# Power.net
KiCad netlist of a schematic drawn in Altium Designer
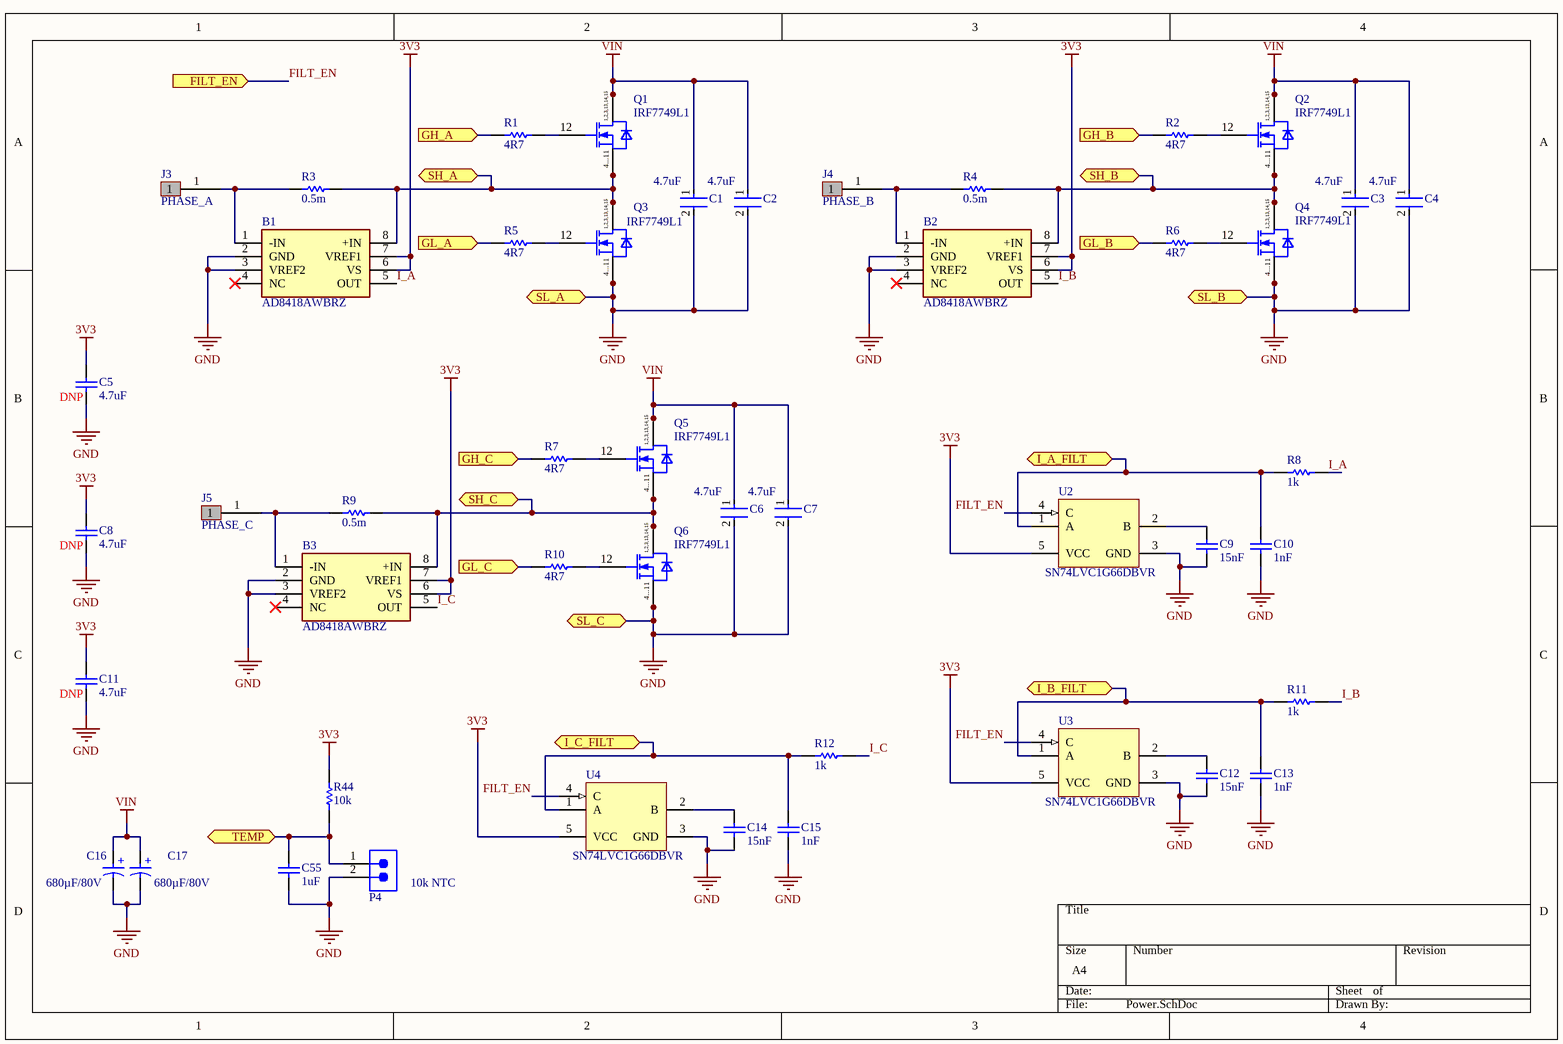
[diagram p0: Power.SchDoc]

(export (version "E")
  (design (tool "Eeschema 10.0.6"))
  (components
    (comp (ref "B1")
      (value "AD8418AWBRZ")
      (footprint "SOP65P490X110-8N")
      (fields (field (name "MOUSER PART NUMBER") "584-AD8418AWBRZ"))
      (libsource (lib "Current_Sense_Amplifiers") (part "AD8418AWBRZ"))
    )
    (comp (ref "B2")
      (value "AD8418AWBRZ")
      (footprint "SOP65P490X110-8N")
      (fields (field (name "MOUSER PART NUMBER") "584-AD8418AWBRZ"))
      (libsource (lib "Current_Sense_Amplifiers") (part "AD8418AWBRZ"))
    )
    (comp (ref "B3")
      (value "AD8418AWBRZ")
      (footprint "SOP65P490X110-8N")
      (fields (field (name "MOUSER PART NUMBER") "584-AD8418AWBRZ"))
      (libsource (lib "Current_Sense_Amplifiers") (part "AD8418AWBRZ"))
    )
    (comp (ref "C1")
      (value "HMK325C7475KN-TE")
      (footprint "FP-1210-L_3_2_0_3-W_2_5_0-IPC_A")
      (description "None")
      (fields (field (name "CAPACITANCE") "4.7uF") (field (name "TOLERANCE") "10%"))
      (libsource (lib "Altium Content Vault") (part "02cd4be3c70576c341d710602a673aa"))
    )
    (comp (ref "C2")
      (value "HMK325C7475KN-TE")
      (footprint "FP-1210-L_3_2_0_3-W_2_5_0-IPC_A")
      (description "None")
      (fields (field (name "CAPACITANCE") "4.7uF") (field (name "TOLERANCE") "10%"))
      (libsource (lib "Altium Content Vault") (part "02cd4be3c70576c341d710602a673aa"))
    )
    (comp (ref "C3")
      (value "HMK325C7475KN-TE")
      (footprint "FP-1210-L_3_2_0_3-W_2_5_0-IPC_A")
      (description "None")
      (fields (field (name "CAPACITANCE") "4.7uF") (field (name "TOLERANCE") "10%"))
      (libsource (lib "Altium Content Vault") (part "02cd4be3c70576c341d710602a673aa"))
    )
    (comp (ref "C4")
      (value "HMK325C7475KN-TE")
      (footprint "FP-1210-L_3_2_0_3-W_2_5_0-IPC_A")
      (description "None")
      (fields (field (name "CAPACITANCE") "4.7uF") (field (name "TOLERANCE") "10%"))
      (libsource (lib "Altium Content Vault") (part "02cd4be3c70576c341d710602a673aa"))
    )
    (comp (ref "C5")
      (value "4.7uF")
      (footprint "Wurth 0603 capacitor")
      (fields (field (name "Comment") "Generic Capacitor 4.7uF 0603"))
      (libsource (lib "Passives") (part "Generic Capacitor 4.7uF 0603"))
    )
    (comp (ref "C6")
      (value "HMK325C7475KN-TE")
      (footprint "FP-1210-L_3_2_0_3-W_2_5_0-IPC_A")
      (description "None")
      (fields (field (name "CAPACITANCE") "4.7uF") (field (name "TOLERANCE") "10%"))
      (libsource (lib "Altium Content Vault") (part "02cd4be3c70576c341d710602a673aa"))
    )
    (comp (ref "C7")
      (value "HMK325C7475KN-TE")
      (footprint "FP-1210-L_3_2_0_3-W_2_5_0-IPC_A")
      (description "None")
      (fields (field (name "CAPACITANCE") "4.7uF") (field (name "TOLERANCE") "10%"))
      (libsource (lib "Altium Content Vault") (part "02cd4be3c70576c341d710602a673aa"))
    )
    (comp (ref "C8")
      (value "4.7uF")
      (footprint "Wurth 0603 capacitor")
      (fields (field (name "Comment") "Generic Capacitor 4.7uF 0603"))
      (libsource (lib "Passives") (part "Generic Capacitor 4.7uF 0603"))
    )
    (comp (ref "C9")
      (value "15nF")
      (footprint "Wurth 0603 capacitor")
      (fields (field (name "Comment") "Generic Capacitor 15nF 0603"))
      (libsource (lib "Passives") (part "Generic Capacitor 15nF 0603"))
    )
    (comp (ref "C10")
      (value "1nF")
      (footprint "Wurth 0603 capacitor")
      (fields (field (name "Comment") "Generic Capacitor 1nF 0603"))
      (libsource (lib "Passives") (part "Generic Capacitor 1nF 0603"))
    )
    (comp (ref "C11")
      (value "4.7uF")
      (footprint "Wurth 0603 capacitor")
      (fields (field (name "Comment") "Generic Capacitor 4.7uF 0603"))
      (libsource (lib "Passives") (part "Generic Capacitor 4.7uF 0603"))
    )
    (comp (ref "C12")
      (value "15nF")
      (footprint "Wurth 0603 capacitor")
      (fields (field (name "Comment") "Generic Capacitor 15nF 0603"))
      (libsource (lib "Passives") (part "Generic Capacitor 15nF 0603"))
    )
    (comp (ref "C13")
      (value "1nF")
      (footprint "Wurth 0603 capacitor")
      (fields (field (name "Comment") "Generic Capacitor 1nF 0603"))
      (libsource (lib "Passives") (part "Generic Capacitor 1nF 0603"))
    )
    (comp (ref "C14")
      (value "15nF")
      (footprint "Wurth 0603 capacitor")
      (fields (field (name "Comment") "Generic Capacitor 15nF 0603"))
      (libsource (lib "Passives") (part "Generic Capacitor 15nF 0603"))
    )
    (comp (ref "C15")
      (value "1nF")
      (footprint "Wurth 0603 capacitor")
      (fields (field (name "Comment") "Generic Capacitor 1nF 0603"))
      (libsource (lib "Passives") (part "Generic Capacitor 1nF 0603"))
    )
    (comp (ref "C16")
      (value "680µF/80V")
      (footprint "WURTH THT CAP D18H25 - sideways")
      (description "Bulk/Capacitor, Aluminum, 80 V, Cap.680 , Dia.18 , Leng.25 ¦Chemi-Con EKY-800ELL681MM25S")
      (fields
        (field (name "MANUFACTURER") "United Chemi-Con")
        (field (name "MANUFACTURER PART NUMBER") "EKY-800ELL681MM25S")
      )
      (libsource (lib "Passives") (part "NCC 680uF/80V TH"))
    )
    (comp (ref "C17")
      (value "680µF/80V")
      (footprint "WURTH THT CAP D18H25 - sideways")
      (description "Bulk/Capacitor, Aluminum, 80 V, Cap.680 , Dia.18 , Leng.25 ¦Chemi-Con EKY-800ELL681MM25S")
      (fields
        (field (name "MANUFACTURER") "United Chemi-Con")
        (field (name "MANUFACTURER PART NUMBER") "EKY-800ELL681MM25S")
      )
      (libsource (lib "Passives") (part "NCC 680uF/80V TH"))
    )
    (comp (ref "C55")
      (value "1uF")
      (footprint "Wurth 0603 capacitor")
      (fields (field (name "Comment") "Generic Capacitor 1uF 0603"))
      (libsource (lib "Passives") (part "Generic Capacitor 1uF 0603"))
    )
    (comp (ref "J3")
      (value "PHASE_A")
      (footprint "Solder Pad 3X4MM")
      (libsource (lib "Connectors") (part "Solder pad"))
    )
    (comp (ref "J4")
      (value "PHASE_B")
      (footprint "Solder Pad 3X4MM")
      (libsource (lib "Connectors") (part "Solder pad"))
    )
    (comp (ref "J5")
      (value "PHASE_C")
      (footprint "Solder Pad 3X4MM")
      (libsource (lib "Connectors") (part "Solder pad"))
    )
    (comp (ref "P4")
      (value "61300211121")
      (footprint "2x1 2.54mm F")
      (description "WR-PHD Pin Header, THT, Vertical, pitch 2.54mm, 1 Row, 2P")
      (fields (field (name "MANUFACTURER") "Wurth Elektronik"))
      (libsource (lib "2.54mm_pin_headers") (part "2P"))
    )
    (comp (ref "Q1")
      (value "IRF7749L1")
      (footprint "INFINEON DIRECTFET-L8-V")
      (fields (field (name "MANUFACTURER") "Infineon Technologies"))
      (libsource (lib "N_CHN_FET") (part "IRF7749L1"))
    )
    (comp (ref "Q2")
      (value "IRF7749L1")
      (footprint "INFINEON DIRECTFET-L8-V")
      (fields (field (name "MANUFACTURER") "Infineon Technologies"))
      (libsource (lib "N_CHN_FET") (part "IRF7749L1"))
    )
    (comp (ref "Q3")
      (value "IRF7749L1")
      (footprint "INFINEON DIRECTFET-L8-V")
      (fields (field (name "MANUFACTURER") "Infineon Technologies"))
      (libsource (lib "N_CHN_FET") (part "IRF7749L1"))
    )
    (comp (ref "Q4")
      (value "IRF7749L1")
      (footprint "INFINEON DIRECTFET-L8-V")
      (fields (field (name "MANUFACTURER") "Infineon Technologies"))
      (libsource (lib "N_CHN_FET") (part "IRF7749L1"))
    )
    (comp (ref "Q5")
      (value "IRF7749L1")
      (footprint "INFINEON DIRECTFET-L8-V")
      (fields (field (name "MANUFACTURER") "Infineon Technologies"))
      (libsource (lib "N_CHN_FET") (part "IRF7749L1"))
    )
    (comp (ref "Q6")
      (value "IRF7749L1")
      (footprint "INFINEON DIRECTFET-L8-V")
      (fields (field (name "MANUFACTURER") "Infineon Technologies"))
      (libsource (lib "N_CHN_FET") (part "IRF7749L1"))
    )
    (comp (ref "R1")
      (value "4R7")
      (footprint "Wurth 0603 Resistor")
      (fields (field (name "Comment") "Generic Resistor 4k7 0603"))
      (libsource (lib "Passives") (part "Generic Resistor 4R7 0603"))
    )
    (comp (ref "R2")
      (value "4R7")
      (footprint "Wurth 0603 Resistor")
      (fields (field (name "Comment") "Generic Resistor 4k7 0603"))
      (libsource (lib "Passives") (part "Generic Resistor 4R7 0603"))
    )
    (comp (ref "R3")
      (value "0.5m")
      (footprint "WURTH 2512 RESISTOR")
      (description "6W 0.5mΩ Patch Splitter ±115ppm/℃ ±1% 2512 Current Sense Resistors / Shunt Resistors ROHS")
      (fields (field (name "Comment") "Yezhan ASR-M-3-0.5F"))
      (libsource (lib "Shunt_Resistors") (part "Yezhan ASR-M-3-0.5F"))
    )
    (comp (ref "R4")
      (value "0.5m")
      (footprint "WURTH 2512 RESISTOR")
      (description "6W 0.5mΩ Patch Splitter ±115ppm/℃ ±1% 2512 Current Sense Resistors / Shunt Resistors ROHS")
      (fields (field (name "Comment") "Yezhan ASR-M-3-0.5F"))
      (libsource (lib "Shunt_Resistors") (part "Yezhan ASR-M-3-0.5F"))
    )
    (comp (ref "R5")
      (value "4R7")
      (footprint "Wurth 0603 Resistor")
      (fields (field (name "Comment") "Generic Resistor 4k7 0603"))
      (libsource (lib "Passives") (part "Generic Resistor 4R7 0603"))
    )
    (comp (ref "R6")
      (value "4R7")
      (footprint "Wurth 0603 Resistor")
      (fields (field (name "Comment") "Generic Resistor 4k7 0603"))
      (libsource (lib "Passives") (part "Generic Resistor 4R7 0603"))
    )
    (comp (ref "R7")
      (value "4R7")
      (footprint "Wurth 0603 Resistor")
      (fields (field (name "Comment") "Generic Resistor 4k7 0603"))
      (libsource (lib "Passives") (part "Generic Resistor 4R7 0603"))
    )
    (comp (ref "R8")
      (value "1k")
      (footprint "Wurth 0603 Resistor")
      (fields (field (name "Comment") "Generic Resistor 1k 0603"))
      (libsource (lib "Passives") (part "Generic Resistor 1k 0603"))
    )
    (comp (ref "R9")
      (value "0.5m")
      (footprint "WURTH 2512 RESISTOR")
      (description "6W 0.5mΩ Patch Splitter ±115ppm/℃ ±1% 2512 Current Sense Resistors / Shunt Resistors ROHS")
      (fields (field (name "Comment") "Yezhan ASR-M-3-0.5F"))
      (libsource (lib "Shunt_Resistors") (part "Yezhan ASR-M-3-0.5F"))
    )
    (comp (ref "R10")
      (value "4R7")
      (footprint "Wurth 0603 Resistor")
      (fields (field (name "Comment") "Generic Resistor 4k7 0603"))
      (libsource (lib "Passives") (part "Generic Resistor 4R7 0603"))
    )
    (comp (ref "R11")
      (value "1k")
      (footprint "Wurth 0603 Resistor")
      (fields (field (name "Comment") "Generic Resistor 1k 0603"))
      (libsource (lib "Passives") (part "Generic Resistor 1k 0603"))
    )
    (comp (ref "R12")
      (value "1k")
      (footprint "Wurth 0603 Resistor")
      (fields (field (name "Comment") "Generic Resistor 1k 0603"))
      (libsource (lib "Passives") (part "Generic Resistor 1k 0603"))
    )
    (comp (ref "R44")
      (value "10k")
      (footprint "Wurth 0603 Resistor")
      (fields (field (name "Comment") "Generic Resistor 10k 0603"))
      (libsource (lib "Passives") (part "Generic Resistor 10k 0603"))
    )
    (comp (ref "U2")
      (value "SN74LVC1G66DBVR")
      (footprint "DBV0005A_L")
      (description "Single Analog Switch, DBV0005A, LARGE T&R")
      (fields
        (field (name "GENERIC PART NUMBER") "SN74LVC1G66")
        (field (name "MANUFACTURER") "Texas Instruments")
      )
      (libsource (lib "Altium Content Vault") (part "TI-SN74XXC1G66-5"))
    )
    (comp (ref "U3")
      (value "SN74LVC1G66DBVR")
      (footprint "DBV0005A_L")
      (description "Single Analog Switch, DBV0005A, LARGE T&R")
      (fields
        (field (name "GENERIC PART NUMBER") "SN74LVC1G66")
        (field (name "MANUFACTURER") "Texas Instruments")
      )
      (libsource (lib "Altium Content Vault") (part "TI-SN74XXC1G66-5"))
    )
    (comp (ref "U4")
      (value "SN74LVC1G66DBVR")
      (footprint "DBV0005A_L")
      (description "Single Analog Switch, DBV0005A, LARGE T&R")
      (fields
        (field (name "GENERIC PART NUMBER") "SN74LVC1G66")
        (field (name "MANUFACTURER") "Texas Instruments")
      )
      (libsource (lib "Altium Content Vault") (part "TI-SN74XXC1G66-5"))
    )
  )
  (nets
    (net (code "1") (name "/FILT_EN") (class "Default")
      (node (ref "U2") (pin "4") (pinfunction "C_4") (pintype "input"))
      (node (ref "U3") (pin "4") (pinfunction "C_4") (pintype "input"))
      (node (ref "U4") (pin "4") (pinfunction "C_4") (pintype "input"))
    )
    (net (code "2") (name "/GH_A") (class "Default")
      (node (ref "R1") (pin "1") (pinfunction "1_1") (pintype "passive"))
    )
    (net (code "3") (name "/GH_B") (class "Default")
      (node (ref "R2") (pin "1") (pinfunction "1_1") (pintype "passive"))
    )
    (net (code "4") (name "/GH_C") (class "Default")
      (node (ref "R7") (pin "1") (pinfunction "1_1") (pintype "passive"))
    )
    (net (code "5") (name "/GL_A") (class "Default")
      (node (ref "R5") (pin "1") (pinfunction "1_1") (pintype "passive"))
    )
    (net (code "6") (name "/GL_B") (class "Default")
      (node (ref "R6") (pin "1") (pinfunction "1_1") (pintype "passive"))
    )
    (net (code "7") (name "/GL_C") (class "Default")
      (node (ref "R10") (pin "1") (pinfunction "1_1") (pintype "passive"))
    )
    (net (code "8") (name "/I_A") (class "Default")
      (node (ref "B1") (pin "5") (pinfunction "OUT_5") (pintype "passive"))
      (node (ref "R8") (pin "2") (pinfunction "2_2") (pintype "passive"))
    )
    (net (code "9") (name "/I_A_FILT") (class "Default")
      (node (ref "C10") (pin "2") (pinfunction "2_2") (pintype "passive"))
      (node (ref "R8") (pin "1") (pinfunction "1_1") (pintype "passive"))
      (node (ref "U2") (pin "1") (pinfunction "A_1") (pintype "passive"))
    )
    (net (code "10") (name "/I_B") (class "Default")
      (node (ref "B2") (pin "5") (pinfunction "OUT_5") (pintype "passive"))
      (node (ref "R11") (pin "2") (pinfunction "2_2") (pintype "passive"))
    )
    (net (code "11") (name "/I_B_FILT") (class "Default")
      (node (ref "C13") (pin "2") (pinfunction "2_2") (pintype "passive"))
      (node (ref "R11") (pin "1") (pinfunction "1_1") (pintype "passive"))
      (node (ref "U3") (pin "1") (pinfunction "A_1") (pintype "passive"))
    )
    (net (code "12") (name "/I_C") (class "Default")
      (node (ref "B3") (pin "5") (pinfunction "OUT_5") (pintype "passive"))
      (node (ref "R12") (pin "2") (pinfunction "2_2") (pintype "passive"))
    )
    (net (code "13") (name "/I_C_FILT") (class "Default")
      (node (ref "C15") (pin "2") (pinfunction "2_2") (pintype "passive"))
      (node (ref "R12") (pin "1") (pinfunction "1_1") (pintype "passive"))
      (node (ref "U4") (pin "1") (pinfunction "A_1") (pintype "passive"))
    )
    (net (code "14") (name "/SH_A") (class "Default")
      (node (ref "B1") (pin "8") (pinfunction "+IN_8") (pintype "passive"))
      (node (ref "Q1") (pin "10") (pinfunction "SOURCE7_10") (pintype "passive"))
      (node (ref "Q1") (pin "11") (pinfunction "SOURCE8_11") (pintype "passive"))
      (node (ref "Q1") (pin "4") (pinfunction "SOURCE1_4") (pintype "passive"))
      (node (ref "Q1") (pin "5") (pinfunction "SOURCE2_5") (pintype "passive"))
      (node (ref "Q1") (pin "6") (pinfunction "SOURCE3_6") (pintype "passive"))
      (node (ref "Q1") (pin "7") (pinfunction "SOURCE4_7") (pintype "passive"))
      (node (ref "Q1") (pin "8") (pinfunction "SOURCE5_8") (pintype "passive"))
      (node (ref "Q1") (pin "9") (pinfunction "SOURCE6_9") (pintype "passive"))
      (node (ref "Q3") (pin "1") (pinfunction "DRAIN1_1") (pintype "passive"))
      (node (ref "Q3") (pin "13") (pinfunction "DRAIN4_13") (pintype "passive"))
      (node (ref "Q3") (pin "14") (pinfunction "DRAIN5_14") (pintype "passive"))
      (node (ref "Q3") (pin "15") (pinfunction "DRAIN6_15") (pintype "passive"))
      (node (ref "Q3") (pin "2") (pinfunction "DRAIN2_2") (pintype "passive"))
      (node (ref "Q3") (pin "3") (pinfunction "DRAIN3_3") (pintype "passive"))
      (node (ref "R3") (pin "2") (pinfunction "2_2") (pintype "passive"))
    )
    (net (code "15") (name "/SH_B") (class "Default")
      (node (ref "B2") (pin "8") (pinfunction "+IN_8") (pintype "passive"))
      (node (ref "Q2") (pin "10") (pinfunction "SOURCE7_10") (pintype "passive"))
      (node (ref "Q2") (pin "11") (pinfunction "SOURCE8_11") (pintype "passive"))
      (node (ref "Q2") (pin "4") (pinfunction "SOURCE1_4") (pintype "passive"))
      (node (ref "Q2") (pin "5") (pinfunction "SOURCE2_5") (pintype "passive"))
      (node (ref "Q2") (pin "6") (pinfunction "SOURCE3_6") (pintype "passive"))
      (node (ref "Q2") (pin "7") (pinfunction "SOURCE4_7") (pintype "passive"))
      (node (ref "Q2") (pin "8") (pinfunction "SOURCE5_8") (pintype "passive"))
      (node (ref "Q2") (pin "9") (pinfunction "SOURCE6_9") (pintype "passive"))
      (node (ref "Q4") (pin "1") (pinfunction "DRAIN1_1") (pintype "passive"))
      (node (ref "Q4") (pin "13") (pinfunction "DRAIN4_13") (pintype "passive"))
      (node (ref "Q4") (pin "14") (pinfunction "DRAIN5_14") (pintype "passive"))
      (node (ref "Q4") (pin "15") (pinfunction "DRAIN6_15") (pintype "passive"))
      (node (ref "Q4") (pin "2") (pinfunction "DRAIN2_2") (pintype "passive"))
      (node (ref "Q4") (pin "3") (pinfunction "DRAIN3_3") (pintype "passive"))
      (node (ref "R4") (pin "2") (pinfunction "2_2") (pintype "passive"))
    )
    (net (code "16") (name "/SH_C") (class "Default")
      (node (ref "B3") (pin "8") (pinfunction "+IN_8") (pintype "passive"))
      (node (ref "Q5") (pin "10") (pinfunction "SOURCE7_10") (pintype "passive"))
      (node (ref "Q5") (pin "11") (pinfunction "SOURCE8_11") (pintype "passive"))
      (node (ref "Q5") (pin "4") (pinfunction "SOURCE1_4") (pintype "passive"))
      (node (ref "Q5") (pin "5") (pinfunction "SOURCE2_5") (pintype "passive"))
      (node (ref "Q5") (pin "6") (pinfunction "SOURCE3_6") (pintype "passive"))
      (node (ref "Q5") (pin "7") (pinfunction "SOURCE4_7") (pintype "passive"))
      (node (ref "Q5") (pin "8") (pinfunction "SOURCE5_8") (pintype "passive"))
      (node (ref "Q5") (pin "9") (pinfunction "SOURCE6_9") (pintype "passive"))
      (node (ref "Q6") (pin "1") (pinfunction "DRAIN1_1") (pintype "passive"))
      (node (ref "Q6") (pin "13") (pinfunction "DRAIN4_13") (pintype "passive"))
      (node (ref "Q6") (pin "14") (pinfunction "DRAIN5_14") (pintype "passive"))
      (node (ref "Q6") (pin "15") (pinfunction "DRAIN6_15") (pintype "passive"))
      (node (ref "Q6") (pin "2") (pinfunction "DRAIN2_2") (pintype "passive"))
      (node (ref "Q6") (pin "3") (pinfunction "DRAIN3_3") (pintype "passive"))
      (node (ref "R9") (pin "2") (pinfunction "2_2") (pintype "passive"))
    )
    (net (code "17") (name "/TEMP") (class "Default")
      (node (ref "C55") (pin "2") (pinfunction "2_2") (pintype "passive"))
      (node (ref "P4") (pin "1") (pinfunction "1_1") (pintype "passive"))
      (node (ref "R44") (pin "1") (pinfunction "1_1") (pintype "passive"))
    )
    (net (code "18") (name "3V3") (class "Default")
      (node (ref "B1") (pin "6") (pinfunction "VS_6") (pintype "passive"))
      (node (ref "B1") (pin "7") (pinfunction "VREF1_7") (pintype "passive"))
      (node (ref "B2") (pin "6") (pinfunction "VS_6") (pintype "passive"))
      (node (ref "B2") (pin "7") (pinfunction "VREF1_7") (pintype "passive"))
      (node (ref "B3") (pin "6") (pinfunction "VS_6") (pintype "passive"))
      (node (ref "B3") (pin "7") (pinfunction "VREF1_7") (pintype "passive"))
      (node (ref "C11") (pin "2") (pinfunction "2_2") (pintype "passive"))
      (node (ref "C5") (pin "2") (pinfunction "2_2") (pintype "passive"))
      (node (ref "C8") (pin "2") (pinfunction "2_2") (pintype "passive"))
      (node (ref "R44") (pin "2") (pinfunction "2_2") (pintype "passive"))
      (node (ref "U2") (pin "5") (pinfunction "VCC_5") (pintype "power_in"))
      (node (ref "U3") (pin "5") (pinfunction "VCC_5") (pintype "power_in"))
      (node (ref "U4") (pin "5") (pinfunction "VCC_5") (pintype "power_in"))
    )
    (net (code "19") (name "GND") (class "Default")
      (node (ref "B1") (pin "2") (pinfunction "GND_2") (pintype "passive"))
      (node (ref "B1") (pin "3") (pinfunction "VREF2_3") (pintype "passive"))
      (node (ref "B2") (pin "2") (pinfunction "GND_2") (pintype "passive"))
      (node (ref "B2") (pin "3") (pinfunction "VREF2_3") (pintype "passive"))
      (node (ref "B3") (pin "2") (pinfunction "GND_2") (pintype "passive"))
      (node (ref "B3") (pin "3") (pinfunction "VREF2_3") (pintype "passive"))
      (node (ref "C1") (pin "2") (pinfunction "2_2") (pintype "passive"))
      (node (ref "C10") (pin "1") (pinfunction "1_1") (pintype "passive"))
      (node (ref "C11") (pin "1") (pinfunction "1_1") (pintype "passive"))
      (node (ref "C12") (pin "1") (pinfunction "1_1") (pintype "passive"))
      (node (ref "C13") (pin "1") (pinfunction "1_1") (pintype "passive"))
      (node (ref "C14") (pin "1") (pinfunction "1_1") (pintype "passive"))
      (node (ref "C15") (pin "1") (pinfunction "1_1") (pintype "passive"))
      (node (ref "C16") (pin "2") (pinfunction "N_2") (pintype "passive"))
      (node (ref "C17") (pin "2") (pinfunction "N_2") (pintype "passive"))
      (node (ref "C2") (pin "2") (pinfunction "2_2") (pintype "passive"))
      (node (ref "C3") (pin "2") (pinfunction "2_2") (pintype "passive"))
      (node (ref "C4") (pin "2") (pinfunction "2_2") (pintype "passive"))
      (node (ref "C5") (pin "1") (pinfunction "1_1") (pintype "passive"))
      (node (ref "C55") (pin "1") (pinfunction "1_1") (pintype "passive"))
      (node (ref "C6") (pin "2") (pinfunction "2_2") (pintype "passive"))
      (node (ref "C7") (pin "2") (pinfunction "2_2") (pintype "passive"))
      (node (ref "C8") (pin "1") (pinfunction "1_1") (pintype "passive"))
      (node (ref "C9") (pin "1") (pinfunction "1_1") (pintype "passive"))
      (node (ref "P4") (pin "2") (pinfunction "2_2") (pintype "passive"))
      (node (ref "Q3") (pin "10") (pinfunction "SOURCE7_10") (pintype "passive"))
      (node (ref "Q3") (pin "11") (pinfunction "SOURCE8_11") (pintype "passive"))
      (node (ref "Q3") (pin "4") (pinfunction "SOURCE1_4") (pintype "passive"))
      (node (ref "Q3") (pin "5") (pinfunction "SOURCE2_5") (pintype "passive"))
      (node (ref "Q3") (pin "6") (pinfunction "SOURCE3_6") (pintype "passive"))
      (node (ref "Q3") (pin "7") (pinfunction "SOURCE4_7") (pintype "passive"))
      (node (ref "Q3") (pin "8") (pinfunction "SOURCE5_8") (pintype "passive"))
      (node (ref "Q3") (pin "9") (pinfunction "SOURCE6_9") (pintype "passive"))
      (node (ref "Q4") (pin "10") (pinfunction "SOURCE7_10") (pintype "passive"))
      (node (ref "Q4") (pin "11") (pinfunction "SOURCE8_11") (pintype "passive"))
      (node (ref "Q4") (pin "4") (pinfunction "SOURCE1_4") (pintype "passive"))
      (node (ref "Q4") (pin "5") (pinfunction "SOURCE2_5") (pintype "passive"))
      (node (ref "Q4") (pin "6") (pinfunction "SOURCE3_6") (pintype "passive"))
      (node (ref "Q4") (pin "7") (pinfunction "SOURCE4_7") (pintype "passive"))
      (node (ref "Q4") (pin "8") (pinfunction "SOURCE5_8") (pintype "passive"))
      (node (ref "Q4") (pin "9") (pinfunction "SOURCE6_9") (pintype "passive"))
      (node (ref "Q6") (pin "10") (pinfunction "SOURCE7_10") (pintype "passive"))
      (node (ref "Q6") (pin "11") (pinfunction "SOURCE8_11") (pintype "passive"))
      (node (ref "Q6") (pin "4") (pinfunction "SOURCE1_4") (pintype "passive"))
      (node (ref "Q6") (pin "5") (pinfunction "SOURCE2_5") (pintype "passive"))
      (node (ref "Q6") (pin "6") (pinfunction "SOURCE3_6") (pintype "passive"))
      (node (ref "Q6") (pin "7") (pinfunction "SOURCE4_7") (pintype "passive"))
      (node (ref "Q6") (pin "8") (pinfunction "SOURCE5_8") (pintype "passive"))
      (node (ref "Q6") (pin "9") (pinfunction "SOURCE6_9") (pintype "passive"))
      (node (ref "U2") (pin "3") (pinfunction "GND_3") (pintype "power_in"))
      (node (ref "U3") (pin "3") (pinfunction "GND_3") (pintype "power_in"))
      (node (ref "U4") (pin "3") (pinfunction "GND_3") (pintype "power_in"))
    )
    (net (code "20") (name "Net-(B1--IN)") (class "Default")
      (node (ref "B1") (pin "1") (pinfunction "-IN_1") (pintype "passive"))
      (node (ref "J3") (pin "1") (pinfunction "1_1") (pintype "passive"))
      (node (ref "R3") (pin "1") (pinfunction "1_1") (pintype "passive"))
    )
    (net (code "21") (name "Net-(B2--IN)") (class "Default")
      (node (ref "B2") (pin "1") (pinfunction "-IN_1") (pintype "passive"))
      (node (ref "J4") (pin "1") (pinfunction "1_1") (pintype "passive"))
      (node (ref "R4") (pin "1") (pinfunction "1_1") (pintype "passive"))
    )
    (net (code "22") (name "Net-(B3--IN)") (class "Default")
      (node (ref "B3") (pin "1") (pinfunction "-IN_1") (pintype "passive"))
      (node (ref "J5") (pin "1") (pinfunction "1_1") (pintype "passive"))
      (node (ref "R9") (pin "1") (pinfunction "1_1") (pintype "passive"))
    )
    (net (code "23") (name "Net-(Q1-GATE)") (class "Default")
      (node (ref "Q1") (pin "12") (pinfunction "GATE_12") (pintype "passive"))
      (node (ref "R1") (pin "2") (pinfunction "2_2") (pintype "passive"))
    )
    (net (code "24") (name "Net-(Q2-GATE)") (class "Default")
      (node (ref "Q2") (pin "12") (pinfunction "GATE_12") (pintype "passive"))
      (node (ref "R2") (pin "2") (pinfunction "2_2") (pintype "passive"))
    )
    (net (code "25") (name "Net-(Q3-GATE)") (class "Default")
      (node (ref "Q3") (pin "12") (pinfunction "GATE_12") (pintype "passive"))
      (node (ref "R5") (pin "2") (pinfunction "2_2") (pintype "passive"))
    )
    (net (code "26") (name "Net-(Q4-GATE)") (class "Default")
      (node (ref "Q4") (pin "12") (pinfunction "GATE_12") (pintype "passive"))
      (node (ref "R6") (pin "2") (pinfunction "2_2") (pintype "passive"))
    )
    (net (code "27") (name "Net-(Q5-GATE)") (class "Default")
      (node (ref "Q5") (pin "12") (pinfunction "GATE_12") (pintype "passive"))
      (node (ref "R7") (pin "2") (pinfunction "2_2") (pintype "passive"))
    )
    (net (code "28") (name "Net-(Q6-GATE)") (class "Default")
      (node (ref "Q6") (pin "12") (pinfunction "GATE_12") (pintype "passive"))
      (node (ref "R10") (pin "2") (pinfunction "2_2") (pintype "passive"))
    )
    (net (code "29") (name "Net-(U2-B)") (class "Default")
      (node (ref "C9") (pin "2") (pinfunction "2_2") (pintype "passive"))
      (node (ref "U2") (pin "2") (pinfunction "B_2") (pintype "passive"))
    )
    (net (code "30") (name "Net-(U3-B)") (class "Default")
      (node (ref "C12") (pin "2") (pinfunction "2_2") (pintype "passive"))
      (node (ref "U3") (pin "2") (pinfunction "B_2") (pintype "passive"))
    )
    (net (code "31") (name "Net-(U4-B)") (class "Default")
      (node (ref "C14") (pin "2") (pinfunction "2_2") (pintype "passive"))
      (node (ref "U4") (pin "2") (pinfunction "B_2") (pintype "passive"))
    )
    (net (code "32") (name "VIN") (class "Default")
      (node (ref "C1") (pin "1") (pinfunction "1_1") (pintype "passive"))
      (node (ref "C16") (pin "1") (pinfunction "P_1") (pintype "passive"))
      (node (ref "C17") (pin "1") (pinfunction "P_1") (pintype "passive"))
      (node (ref "C2") (pin "1") (pinfunction "1_1") (pintype "passive"))
      (node (ref "C3") (pin "1") (pinfunction "1_1") (pintype "passive"))
      (node (ref "C4") (pin "1") (pinfunction "1_1") (pintype "passive"))
      (node (ref "C6") (pin "1") (pinfunction "1_1") (pintype "passive"))
      (node (ref "C7") (pin "1") (pinfunction "1_1") (pintype "passive"))
      (node (ref "Q1") (pin "1") (pinfunction "DRAIN1_1") (pintype "passive"))
      (node (ref "Q1") (pin "13") (pinfunction "DRAIN4_13") (pintype "passive"))
      (node (ref "Q1") (pin "14") (pinfunction "DRAIN5_14") (pintype "passive"))
      (node (ref "Q1") (pin "15") (pinfunction "DRAIN6_15") (pintype "passive"))
      (node (ref "Q1") (pin "2") (pinfunction "DRAIN2_2") (pintype "passive"))
      (node (ref "Q1") (pin "3") (pinfunction "DRAIN3_3") (pintype "passive"))
      (node (ref "Q2") (pin "1") (pinfunction "DRAIN1_1") (pintype "passive"))
      (node (ref "Q2") (pin "13") (pinfunction "DRAIN4_13") (pintype "passive"))
      (node (ref "Q2") (pin "14") (pinfunction "DRAIN5_14") (pintype "passive"))
      (node (ref "Q2") (pin "15") (pinfunction "DRAIN6_15") (pintype "passive"))
      (node (ref "Q2") (pin "2") (pinfunction "DRAIN2_2") (pintype "passive"))
      (node (ref "Q2") (pin "3") (pinfunction "DRAIN3_3") (pintype "passive"))
      (node (ref "Q5") (pin "1") (pinfunction "DRAIN1_1") (pintype "passive"))
      (node (ref "Q5") (pin "13") (pinfunction "DRAIN4_13") (pintype "passive"))
      (node (ref "Q5") (pin "14") (pinfunction "DRAIN5_14") (pintype "passive"))
      (node (ref "Q5") (pin "15") (pinfunction "DRAIN6_15") (pintype "passive"))
      (node (ref "Q5") (pin "2") (pinfunction "DRAIN2_2") (pintype "passive"))
      (node (ref "Q5") (pin "3") (pinfunction "DRAIN3_3") (pintype "passive"))
    )
    (net (code "33") (name "unconnected-(B1-NC-Pad4)") (class "Default")
      (node (ref "B1") (pin "4") (pinfunction "NC_4") (pintype "passive+no_connect"))
    )
    (net (code "34") (name "unconnected-(B2-NC-Pad4)") (class "Default")
      (node (ref "B2") (pin "4") (pinfunction "NC_4") (pintype "passive+no_connect"))
    )
    (net (code "35") (name "unconnected-(B3-NC-Pad4)") (class "Default")
      (node (ref "B3") (pin "4") (pinfunction "NC_4") (pintype "passive+no_connect"))
    )
  )
)
